# eBox_relay.net
KiCad netlist of a schematic drawn in Altium Designer
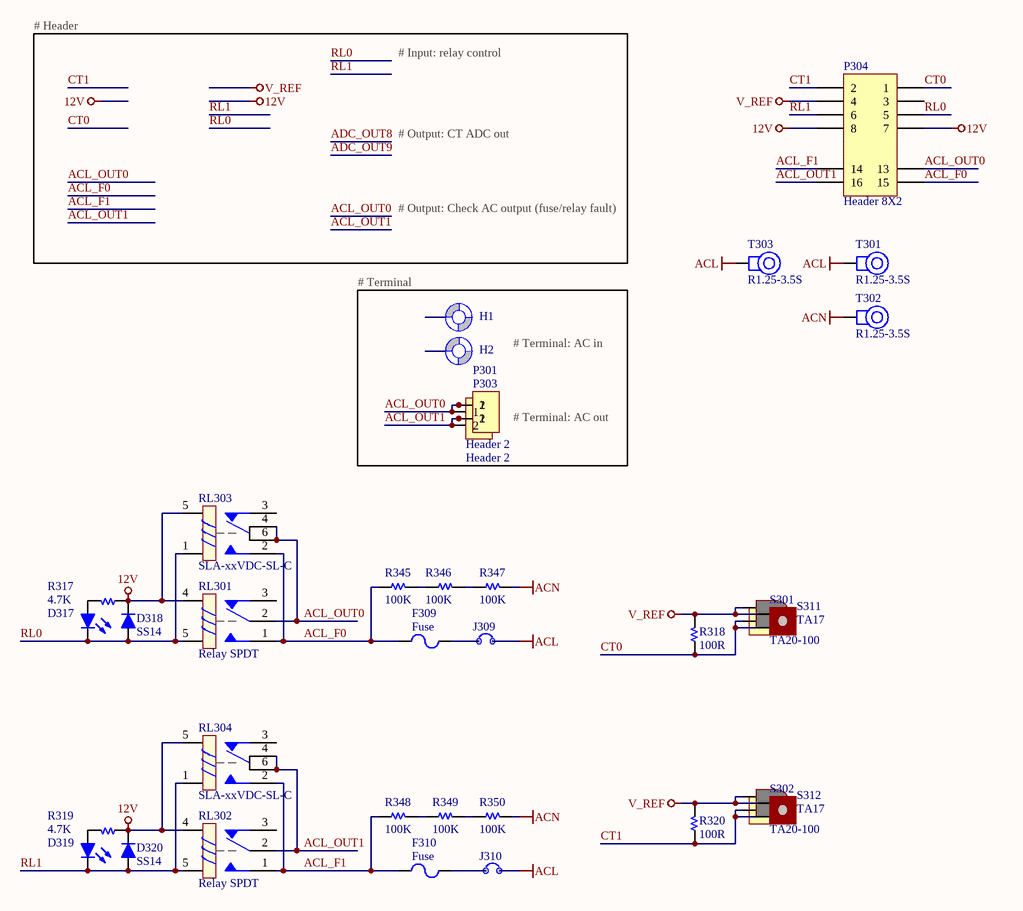
[diagram p0: eBox_relay.SchDoc]

(export (version "E")
  (design (tool "Eeschema 10.0.6"))
  (components
    (comp (ref "D317")
      (value "Led")
      (footprint "LED 3MM - green")
      (description "LED GREEN DIFFUSED 3MM ROUND T/H")
      (libsource (lib "chipfc_altium_libs") (part "Led"))
    )
    (comp (ref "D318")
      (value "SS14")
      (footprint "DO-214AC (SMA) L")
      (description "DIODE SCHOTTKY 40V 1A SMA")
      (libsource (lib "chipfc_altium_libs") (part "Diode"))
    )
    (comp (ref "D319")
      (value "Led")
      (footprint "LED 3MM - green")
      (description "LED GREEN DIFFUSED 3MM ROUND T/H")
      (libsource (lib "chipfc_altium_libs") (part "Led"))
    )
    (comp (ref "D320")
      (value "SS14")
      (footprint "DO-214AC (SMA) L")
      (description "DIODE SCHOTTKY 40V 1A SMA")
      (libsource (lib "chipfc_altium_libs") (part "Diode"))
    )
    (comp (ref "F309")
      (value "Fuse")
      (footprint "FUSE 2 DIP 0520 BOX")
      (libsource (lib "chipfc_altium_libs") (part "Fuse"))
    )
    (comp (ref "F310")
      (value "Fuse")
      (footprint "FUSE 2 DIP 0520 BOX")
      (libsource (lib "chipfc_altium_libs") (part "Fuse"))
    )
    (comp (ref "H1")
      (value "Screw Hole")
      (footprint "SCREW/3.2/7.0/M")
      (libsource (lib "chipfc_altium_libs") (part "Screw Hole"))
    )
    (comp (ref "H2")
      (value "Screw Hole")
      (footprint "SCREW/3.2/7.0/M")
      (libsource (lib "chipfc_altium_libs") (part "Screw Hole"))
    )
    (comp (ref "J309")
      (value "JUMP 2 CUSTOM")
      (footprint "JUMP/2/Custom")
      (libsource (lib "chipfc_altium_libs") (part "JUMP 2 CUSTOM"))
    )
    (comp (ref "J310")
      (value "JUMP 2 CUSTOM")
      (footprint "JUMP/2/Custom")
      (libsource (lib "chipfc_altium_libs") (part "JUMP 2 CUSTOM"))
    )
    (comp (ref "P301")
      (value "Header 2")
      (footprint "HDR/Terminal/2/KF1000")
      (description "Header, 2-Pin")
      (libsource (lib "chipfc_altium_libs") (part "Header 2"))
    )
    (comp (ref "P303")
      (value "Header 2")
      (footprint "HDR/Terminal/2/KF55C-10")
      (description "Header, 2-Pin")
      (libsource (lib "chipfc_altium_libs") (part "Header 2"))
    )
    (comp (ref "P304")
      (value "Header 8X2")
      (footprint "HDR/Header/16/DL/EDGE")
      (description "Header, 8-Pin, Dual row")
      (libsource (lib "chipfc_altium_libs") (part "Header 8X2"))
    )
    (comp (ref "P305")
      (value "Header 2")
      (footprint "HDR/Terminal/2/KF1000")
      (description "Header, 2-Pin")
      (libsource (lib "") (part "Header 2_1"))
    )
    (comp (ref "R317")
      (value "4.7K")
      (footprint "R 0603")
      (description "RES SMD 4.7K OHM 1% 1/10W 0805")
      (libsource (lib "chipfc_altium_libs") (part "Resistor"))
    )
    (comp (ref "R318")
      (value "100R")
      (footprint "R 0805")
      (description "RES SMD 100 OHM 1% 1/10W 0805")
      (libsource (lib "chipfc_altium_libs") (part "Resistor"))
    )
    (comp (ref "R319")
      (value "4.7K")
      (footprint "R 0603")
      (description "RES SMD 4.7K OHM 1% 1/10W 0805")
      (libsource (lib "chipfc_altium_libs") (part "Resistor"))
    )
    (comp (ref "R320")
      (value "100R")
      (footprint "R 0805")
      (description "RES SMD 100 OHM 1% 1/10W 0805")
      (libsource (lib "chipfc_altium_libs") (part "Resistor"))
    )
    (comp (ref "R345")
      (value "100K")
      (footprint "R 1206")
      (description "RES SMD 10K OHM 5% 1/4W 1206")
      (libsource (lib "chipfc_altium_libs") (part "Resistor"))
    )
    (comp (ref "R346")
      (value "100K")
      (footprint "R 1206")
      (description "RES SMD 10K OHM 5% 1/4W 1206")
      (libsource (lib "chipfc_altium_libs") (part "Resistor"))
    )
    (comp (ref "R347")
      (value "100K")
      (footprint "R 1206")
      (description "RES SMD 10K OHM 5% 1/4W 1206")
      (libsource (lib "chipfc_altium_libs") (part "Resistor"))
    )
    (comp (ref "R348")
      (value "100K")
      (footprint "R 1206")
      (description "RES SMD 10K OHM 5% 1/4W 1206")
      (libsource (lib "chipfc_altium_libs") (part "Resistor"))
    )
    (comp (ref "R349")
      (value "100K")
      (footprint "R 1206")
      (description "RES SMD 10K OHM 5% 1/4W 1206")
      (libsource (lib "chipfc_altium_libs") (part "Resistor"))
    )
    (comp (ref "R350")
      (value "100K")
      (footprint "R 1206")
      (description "RES SMD 10K OHM 5% 1/4W 1206")
      (libsource (lib "chipfc_altium_libs") (part "Resistor"))
    )
    (comp (ref "RL301")
      (value "Relay SPDT")
      (footprint "RL_SPDT_MIX")
      (libsource (lib "chipfc_altium_libs") (part "Relay SPDT"))
    )
    (comp (ref "RL302")
      (value "Relay SPDT")
      (footprint "RL_SPDT_MIX")
      (libsource (lib "chipfc_altium_libs") (part "Relay SPDT"))
    )
    (comp (ref "RL303")
      (value "SLA-xxVDC-SL-C")
      (footprint "RL_SPDT_30A")
      (libsource (lib "chipfc_altium_libs") (part "Relay SPDT_SLA"))
    )
    (comp (ref "RL304")
      (value "SLA-xxVDC-SL-C")
      (footprint "RL_SPDT_30A")
      (libsource (lib "chipfc_altium_libs") (part "Relay SPDT_SLA"))
    )
    (comp (ref "S301")
      (value "TA20-100")
      (footprint "TA20-100")
      (libsource (lib "chipfc_altium_libs") (part "TA20-100"))
    )
    (comp (ref "S302")
      (value "TA20-100")
      (footprint "TA20-100")
      (libsource (lib "chipfc_altium_libs") (part "TA20-100"))
    )
    (comp (ref "S309")
      (value "TA12-200")
      (footprint "TA12")
      (description "CURR SENSE 1:2000 5A T/H")
      (libsource (lib "chipfc_altium_libs") (part "TA12"))
    )
    (comp (ref "S310")
      (value "NA")
      (footprint "TA12")
      (description "CURR SENSE 1:2000 5A T/H")
      (fields (field (name "PART NO") "TA12-200"))
      (libsource (lib "chipfc_altium_libs") (part "TA12"))
    )
    (comp (ref "S311") (value "TA17") (footprint "TA17") (libsource (lib "chipfc_altium_libs") (part "TA17")))
    (comp (ref "S312") (value "TA17") (footprint "TA17") (libsource (lib "chipfc_altium_libs") (part "TA17")))
    (comp (ref "T301")
      (value "R1.25-3.5S")
      (footprint "R1.25-3.5S")
      (libsource (lib "chipfc_altium_libs") (part "R1.25-3.5S"))
    )
    (comp (ref "T302")
      (value "R1.25-3.5S")
      (footprint "R1.25-3.5S")
      (libsource (lib "chipfc_altium_libs") (part "R1.25-3.5S"))
    )
    (comp (ref "T303")
      (value "R1.25-3.5S")
      (footprint "R1.25-3.5S")
      (libsource (lib "chipfc_altium_libs") (part "R1.25-3.5S"))
    )
  )
  (nets
    (net (code "1") (name "/ACL_F0") (class "Default")
      (node (ref "F309") (pin "1") (pinfunction "1_1") (pintype "passive"))
      (node (ref "P304") (pin "15") (pinfunction "15_15") (pintype "passive"))
      (node (ref "R345") (pin "1") (pinfunction "1_1") (pintype "passive"))
      (node (ref "RL301") (pin "1") (pinfunction "COM_1") (pintype "passive"))
      (node (ref "RL303") (pin "2") (pinfunction "NO_2") (pintype "passive"))
    )
    (net (code "2") (name "/ACL_F1") (class "Default")
      (node (ref "F310") (pin "1") (pinfunction "1_1") (pintype "passive"))
      (node (ref "P304") (pin "14") (pinfunction "14_14") (pintype "passive"))
      (node (ref "R348") (pin "1") (pinfunction "1_1") (pintype "passive"))
      (node (ref "RL302") (pin "1") (pinfunction "COM_1") (pintype "passive"))
      (node (ref "RL304") (pin "2") (pinfunction "NO_2") (pintype "passive"))
    )
    (net (code "3") (name "/ACL_OUT0") (class "Default")
      (node (ref "P301") (pin "1") (pinfunction "1_1") (pintype "passive"))
      (node (ref "P303") (pin "1") (pinfunction "1_1") (pintype "passive"))
      (node (ref "P304") (pin "13") (pinfunction "13_13") (pintype "passive"))
      (node (ref "P305") (pin "2") (pinfunction "2_2") (pintype "passive"))
      (node (ref "RL301") (pin "2") (pinfunction "NO_2") (pintype "passive"))
      (node (ref "RL303") (pin "4") (pinfunction "COM_4") (pintype "passive"))
      (node (ref "RL303") (pin "6") (pinfunction "COM_6") (pintype "passive"))
    )
    (net (code "4") (name "/ACL_OUT1") (class "Default")
      (node (ref "P301") (pin "2") (pinfunction "2_2") (pintype "passive"))
      (node (ref "P303") (pin "2") (pinfunction "2_2") (pintype "passive"))
      (node (ref "P304") (pin "16") (pinfunction "16_16") (pintype "passive"))
      (node (ref "P305") (pin "1") (pinfunction "1_1") (pintype "passive"))
      (node (ref "RL302") (pin "2") (pinfunction "NO_2") (pintype "passive"))
      (node (ref "RL304") (pin "4") (pinfunction "COM_4") (pintype "passive"))
      (node (ref "RL304") (pin "6") (pinfunction "COM_6") (pintype "passive"))
    )
    (net (code "7") (name "/CT0") (class "Default")
      (node (ref "P304") (pin "1") (pinfunction "1_1") (pintype "passive"))
      (node (ref "R318") (pin "1") (pinfunction "1_1") (pintype "passive"))
      (node (ref "S301") (pin "4") (pinfunction "4_4") (pintype "passive"))
      (node (ref "S309") (pin "2") (pinfunction "2_2") (pintype "passive"))
      (node (ref "S311") (pin "2") (pinfunction "2_2") (pintype "passive"))
    )
    (net (code "8") (name "/CT1") (class "Default")
      (node (ref "P304") (pin "2") (pinfunction "2_2") (pintype "passive"))
      (node (ref "R320") (pin "1") (pinfunction "1_1") (pintype "passive"))
      (node (ref "S302") (pin "4") (pinfunction "4_4") (pintype "passive"))
      (node (ref "S310") (pin "2") (pinfunction "2_2") (pintype "passive"))
      (node (ref "S312") (pin "2") (pinfunction "2_2") (pintype "passive"))
    )
    (net (code "9") (name "/RL0") (class "Default")
      (node (ref "D317") (pin "2") (pinfunction "K_2") (pintype "passive"))
      (node (ref "D318") (pin "1") (pinfunction "A_1") (pintype "passive"))
      (node (ref "P304") (pin "5") (pinfunction "5_5") (pintype "passive"))
      (node (ref "RL301") (pin "5") (pinfunction "COIL2_5") (pintype "passive"))
      (node (ref "RL303") (pin "1") (pinfunction "COIL1_1") (pintype "passive"))
    )
    (net (code "10") (name "/RL1") (class "Default")
      (node (ref "D319") (pin "2") (pinfunction "K_2") (pintype "passive"))
      (node (ref "D320") (pin "1") (pinfunction "A_1") (pintype "passive"))
      (node (ref "P304") (pin "6") (pinfunction "6_6") (pintype "passive"))
      (node (ref "RL302") (pin "5") (pinfunction "COIL2_5") (pintype "passive"))
      (node (ref "RL304") (pin "1") (pinfunction "COIL1_1") (pintype "passive"))
    )
    (net (code "11") (name "12V") (class "Default")
      (node (ref "D318") (pin "2") (pinfunction "K_2") (pintype "passive"))
      (node (ref "D320") (pin "2") (pinfunction "K_2") (pintype "passive"))
      (node (ref "P304") (pin "7") (pinfunction "7_7") (pintype "passive"))
      (node (ref "P304") (pin "8") (pinfunction "8_8") (pintype "passive"))
      (node (ref "R317") (pin "1") (pinfunction "1_1") (pintype "passive"))
      (node (ref "R319") (pin "1") (pinfunction "1_1") (pintype "passive"))
      (node (ref "RL301") (pin "4") (pinfunction "COIL1_4") (pintype "passive"))
      (node (ref "RL302") (pin "4") (pinfunction "COIL1_4") (pintype "passive"))
      (node (ref "RL303") (pin "5") (pinfunction "COIL2_5") (pintype "passive"))
      (node (ref "RL304") (pin "5") (pinfunction "COIL2_5") (pintype "passive"))
    )
    (net (code "12") (name "ACL") (class "Default")
      (node (ref "J309") (pin "2") (pinfunction "2_2") (pintype "passive"))
      (node (ref "J310") (pin "2") (pinfunction "2_2") (pintype "passive"))
      (node (ref "T301") (pin "1") (pinfunction "1_1") (pintype "passive"))
      (node (ref "T303") (pin "1") (pinfunction "1_1") (pintype "passive"))
    )
    (net (code "13") (name "ACN") (class "Default")
      (node (ref "R347") (pin "2") (pinfunction "2_2") (pintype "passive"))
      (node (ref "R350") (pin "2") (pinfunction "2_2") (pintype "passive"))
      (node (ref "T302") (pin "1") (pinfunction "1_1") (pintype "passive"))
    )
    (net (code "14") (name "Net-(D317-A)") (class "Default")
      (node (ref "D317") (pin "1") (pinfunction "A_1") (pintype "passive"))
      (node (ref "R317") (pin "2") (pinfunction "2_2") (pintype "passive"))
    )
    (net (code "15") (name "Net-(D319-A)") (class "Default")
      (node (ref "D319") (pin "1") (pinfunction "A_1") (pintype "passive"))
      (node (ref "R319") (pin "2") (pinfunction "2_2") (pintype "passive"))
    )
    (net (code "16") (name "Net-(F309-Pad2)") (class "Default")
      (node (ref "F309") (pin "2") (pinfunction "2_2") (pintype "passive"))
      (node (ref "J309") (pin "1") (pinfunction "1_1") (pintype "passive"))
    )
    (net (code "17") (name "Net-(F310-Pad2)") (class "Default")
      (node (ref "F310") (pin "2") (pinfunction "2_2") (pintype "passive"))
      (node (ref "J310") (pin "1") (pinfunction "1_1") (pintype "passive"))
    )
    (net (code "18") (name "Net-(R345-Pad2)") (class "Default")
      (node (ref "R345") (pin "2") (pinfunction "2_2") (pintype "passive"))
      (node (ref "R346") (pin "1") (pinfunction "1_1") (pintype "passive"))
    )
    (net (code "19") (name "Net-(R346-Pad2)") (class "Default")
      (node (ref "R346") (pin "2") (pinfunction "2_2") (pintype "passive"))
      (node (ref "R347") (pin "1") (pinfunction "1_1") (pintype "passive"))
    )
    (net (code "20") (name "Net-(R348-Pad2)") (class "Default")
      (node (ref "R348") (pin "2") (pinfunction "2_2") (pintype "passive"))
      (node (ref "R349") (pin "1") (pinfunction "1_1") (pintype "passive"))
    )
    (net (code "21") (name "Net-(R349-Pad2)") (class "Default")
      (node (ref "R349") (pin "2") (pinfunction "2_2") (pintype "passive"))
      (node (ref "R350") (pin "1") (pinfunction "1_1") (pintype "passive"))
    )
    (net (code "22") (name "V_REF") (class "Default")
      (node (ref "P304") (pin "4") (pinfunction "4_4") (pintype "passive"))
      (node (ref "R318") (pin "2") (pinfunction "2_2") (pintype "passive"))
      (node (ref "R320") (pin "2") (pinfunction "2_2") (pintype "passive"))
      (node (ref "S301") (pin "3") (pinfunction "3_3") (pintype "passive"))
      (node (ref "S302") (pin "3") (pinfunction "3_3") (pintype "passive"))
      (node (ref "S309") (pin "1") (pinfunction "1_1") (pintype "passive"))
      (node (ref "S310") (pin "1") (pinfunction "1_1") (pintype "passive"))
      (node (ref "S311") (pin "1") (pinfunction "1_1") (pintype "passive"))
      (node (ref "S312") (pin "1") (pinfunction "1_1") (pintype "passive"))
    )
    (net (code "23") (name "unconnected-(H1-Screw-Pad1)") (class "Default")
      (node (ref "H1") (pin "1") (pinfunction "Screw_1") (pintype "passive"))
    )
    (net (code "24") (name "unconnected-(H2-Screw-Pad1)") (class "Default")
      (node (ref "H2") (pin "1") (pinfunction "Screw_1") (pintype "passive"))
    )
    (net (code "25") (name "unconnected-(P304-Pad3)") (class "Default")
      (node (ref "P304") (pin "3") (pinfunction "3_3") (pintype "passive"))
    )
    (net (code "26") (name "unconnected-(P304-Pad9)") (class "Default")
      (node (ref "P304") (pin "9") (pinfunction "9_9") (pintype "passive"))
    )
    (net (code "27") (name "unconnected-(P304-Pad10)") (class "Default")
      (node (ref "P304") (pin "10") (pinfunction "10_10") (pintype "passive"))
    )
    (net (code "28") (name "unconnected-(P304-Pad11)") (class "Default")
      (node (ref "P304") (pin "11") (pinfunction "11_11") (pintype "passive"))
    )
    (net (code "29") (name "unconnected-(P304-Pad12)") (class "Default")
      (node (ref "P304") (pin "12") (pinfunction "12_12") (pintype "passive"))
    )
    (net (code "30") (name "unconnected-(RL301-NC-Pad3)") (class "Default")
      (node (ref "RL301") (pin "3") (pinfunction "NC_3") (pintype "passive"))
    )
    (net (code "31") (name "unconnected-(RL302-NC-Pad3)") (class "Default")
      (node (ref "RL302") (pin "3") (pinfunction "NC_3") (pintype "passive"))
    )
    (net (code "32") (name "unconnected-(RL303-NC-Pad3)") (class "Default")
      (node (ref "RL303") (pin "3") (pinfunction "NC_3") (pintype "passive"))
    )
    (net (code "33") (name "unconnected-(RL304-NC-Pad3)") (class "Default")
      (node (ref "RL304") (pin "3") (pinfunction "NC_3") (pintype "passive"))
    )
  )
)
